# Temperature_sensor_Board2.net
KiCad netlist of a schematic drawn in EAGLE
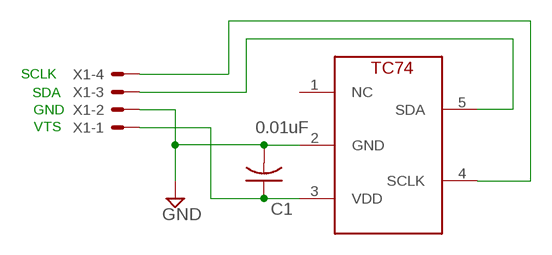
[diagram p0: schematic, sheet 1]

(export (version "E")
  (design (tool "Eeschema 10.0.6"))
  (components
    (comp (ref "C1")
      (value "0.01uF")
      (footprint "eagle-import:C0805")
      (libsource (lib "eagle-import") (part "C-USC0805"))
    )
    (comp (ref "S1")
      (value "TC74")
      (footprint "eagle-import:SOT23-5L")
      (libsource (lib "eagle-import") (part "TC74"))
    )
    (comp (ref "X1")
      (value "22-23-2041")
      (footprint "eagle-import:22-23-2041")
      (fields (field (name "MF") "MOLEX"))
      (libsource (lib "eagle-import") (part "22-23-2041"))
    )
  )
  (nets
    (net (code "1") (name "GND") (class "Default")
      (node (ref "C1") (pin "2") (pinfunction "2_2") (pintype "passive"))
      (node (ref "S1") (pin "2") (pinfunction "GND_2") (pintype "bidirectional"))
      (node (ref "X1") (pin "2") (pinfunction "S_2") (pintype "passive"))
    )
    (net (code "2") (name "Net-(S1-SCLK)") (class "Default")
      (node (ref "S1") (pin "4") (pinfunction "SCLK_4") (pintype "bidirectional"))
      (node (ref "X1") (pin "4") (pinfunction "S_4") (pintype "passive"))
    )
    (net (code "3") (name "Net-(S1-SDA)") (class "Default")
      (node (ref "S1") (pin "5") (pinfunction "SDA_5") (pintype "bidirectional"))
      (node (ref "X1") (pin "3") (pinfunction "S_3") (pintype "passive"))
    )
    (net (code "4") (name "Net-(S1-VDD)") (class "Default")
      (node (ref "C1") (pin "1") (pinfunction "1_1") (pintype "passive"))
      (node (ref "S1") (pin "3") (pinfunction "VDD_3") (pintype "bidirectional"))
      (node (ref "X1") (pin "1") (pinfunction "S_1") (pintype "passive"))
    )
    (net (code "5") (name "unconnected-(S1-NC-Pad1)") (class "Default")
      (node (ref "S1") (pin "1") (pinfunction "NC_1") (pintype "bidirectional"))
    )
  )
)
